# final_sensor_sch_v3.net
KiCad netlist of a schematic drawn in Altium Designer
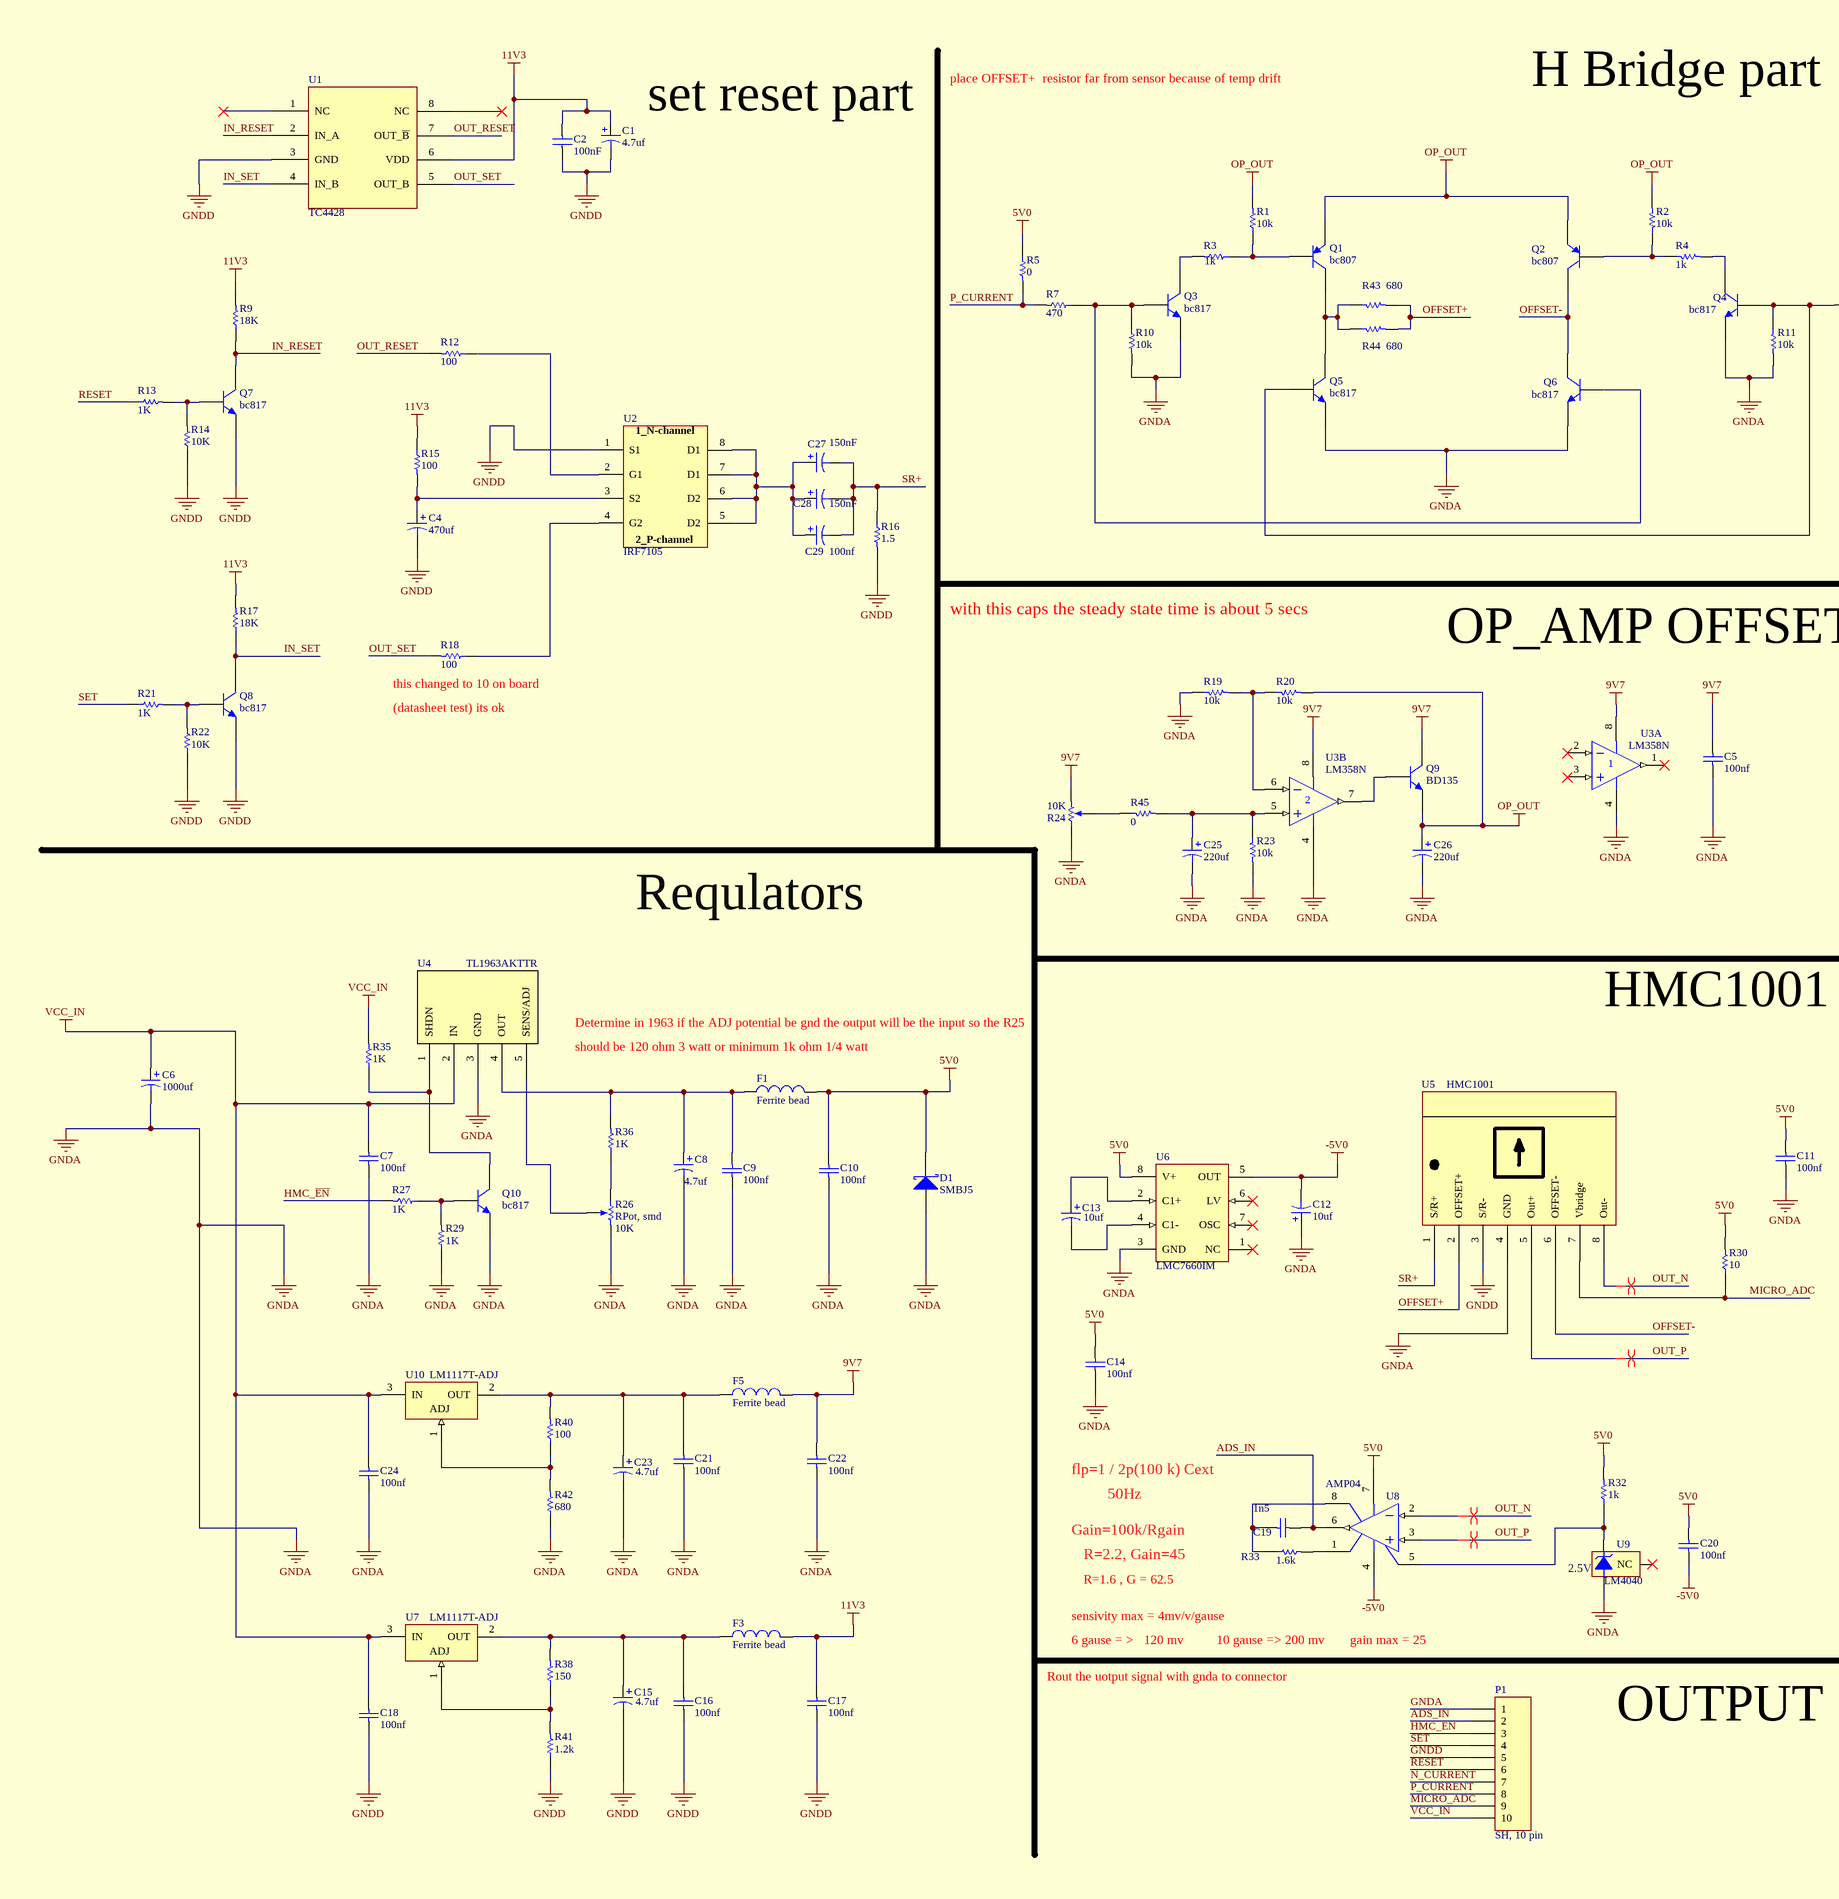
[diagram p0: final_sensor_sch_v3.SchDoc, left]
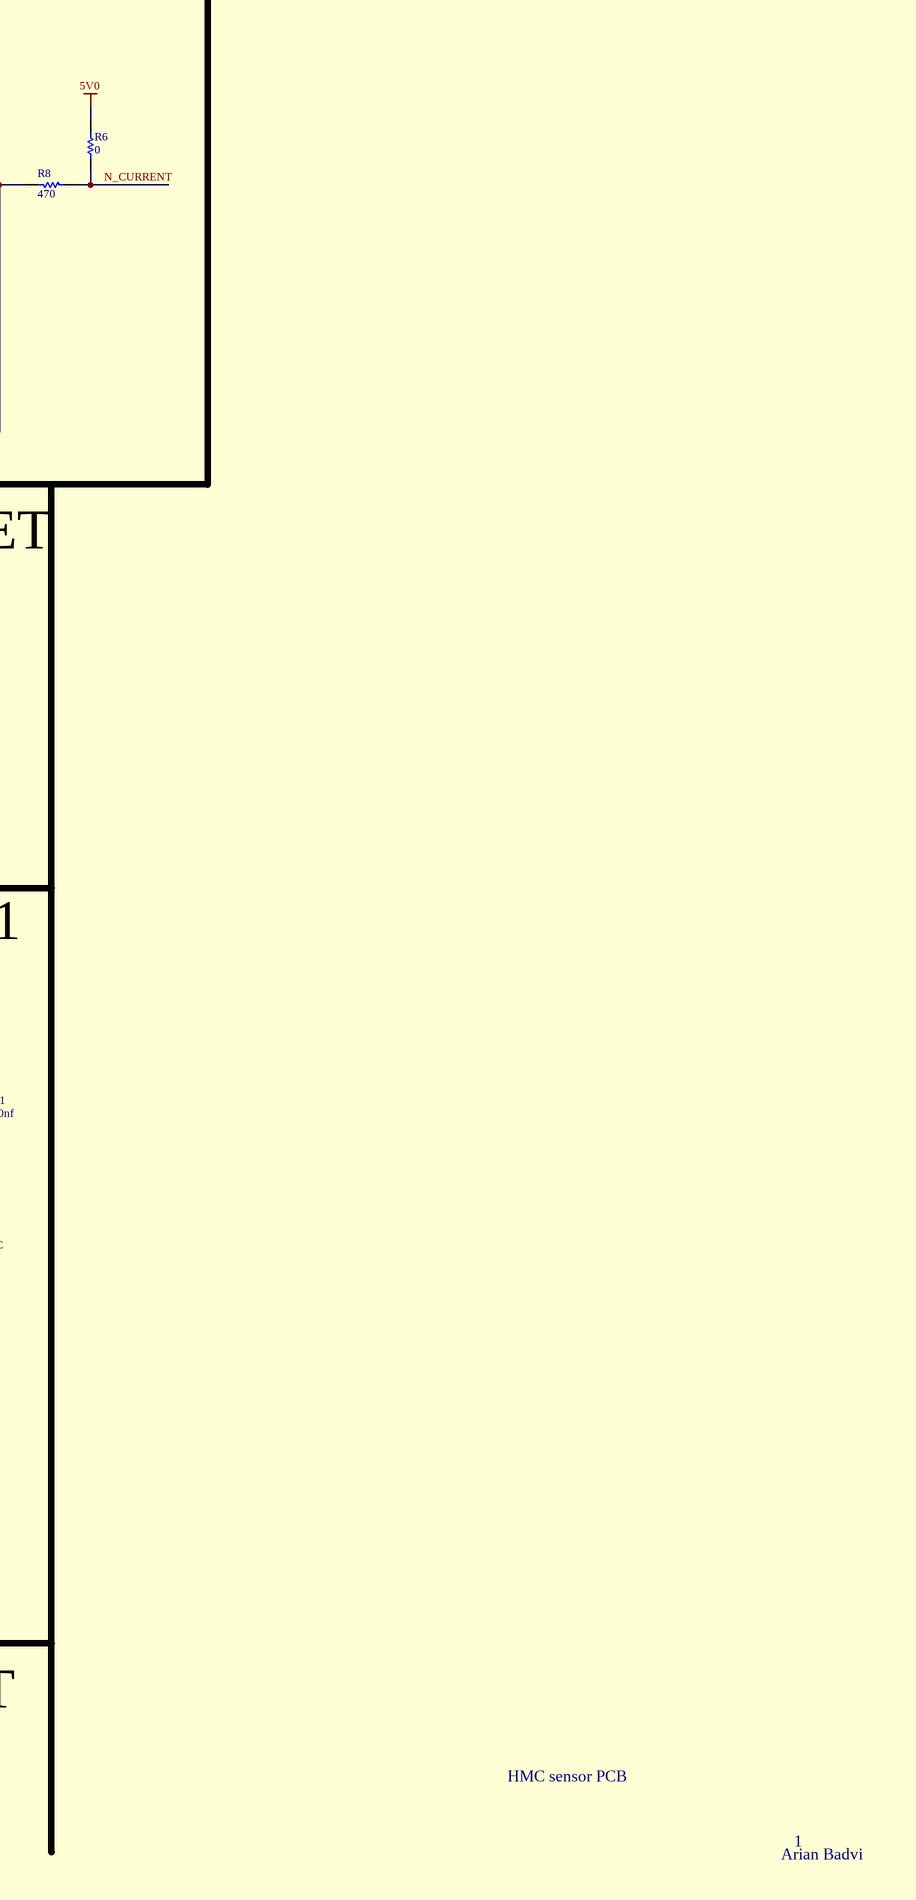
[diagram p1: final_sensor_sch_v3.SchDoc, right]

(export (version "E")
  (design (tool "Eeschema 10.0.6"))
  (components
    (comp (ref "C1")
      (value "4.7uf")
      (footprint "cap_smd_a")
      (description "Polarized Capacitor (Radial)")
      (fields (field (name "PUBLISHER") "Altium Limited"))
      (libsource (lib "") (part "Cap Pol1_1"))
    )
    (comp (ref "C2")
      (value "100nF")
      (footprint "1206")
      (description "Capacitor")
      (fields (field (name "PUBLISHER") "Altium Limited"))
      (libsource (lib "Miscellaneous Devices") (part "Cap"))
    )
    (comp (ref "C4")
      (value "470uf")
      (footprint "cap_smd_d")
      (description "TAN CAP D SIZE")
      (fields (field (name "PUBLISHER") "Altium Limited"))
      (libsource (lib "Miscellaneous Devices") (part "Cap Pol1"))
    )
    (comp (ref "C5")
      (value "100nf")
      (footprint "1206")
      (description "Capacitor")
      (fields (field (name "PUBLISHER") "Altium Limited"))
      (libsource (lib "Miscellaneous Devices") (part "Cap"))
    )
    (comp (ref "C6")
      (value "1000uf")
      (footprint "c_cyl_smd")
      (description "electrolytic smd cap")
      (fields (field (name "PUBLISHER") "Altium Limited"))
      (libsource (lib "Miscellaneous Devices") (part "Cap Pol1"))
    )
    (comp (ref "C7")
      (value "100nf")
      (footprint "1206")
      (description "Capacitor")
      (fields (field (name "PUBLISHER") "Altium Limited"))
      (libsource (lib "Miscellaneous Devices") (part "Cap"))
    )
    (comp (ref "C8")
      (value "4.7uf")
      (footprint "cap_smd_a")
      (description "Polarized Capacitor (Radial)")
      (fields (field (name "PUBLISHER") "Altium Limited"))
      (libsource (lib "Miscellaneous Devices") (part "Cap Pol1"))
    )
    (comp (ref "C9")
      (value "100nf")
      (footprint "1206")
      (description "Capacitor")
      (fields (field (name "PUBLISHER") "Altium Limited"))
      (libsource (lib "Miscellaneous Devices") (part "Cap"))
    )
    (comp (ref "C10")
      (value "100nf")
      (footprint "1206")
      (description "Capacitor")
      (fields (field (name "PUBLISHER") "Altium Limited"))
      (libsource (lib "Miscellaneous Devices") (part "Cap"))
    )
    (comp (ref "C11")
      (value "100nf")
      (footprint "1206")
      (description "Capacitor")
      (fields (field (name "PUBLISHER") "Altium Limited"))
      (libsource (lib "Miscellaneous Devices") (part "Cap"))
    )
    (comp (ref "C12")
      (value "10uf")
      (footprint "cap_smd_a")
      (description "Polarized Capacitor (Radial)")
      (fields (field (name "PUBLISHER") "Altium Limited"))
      (libsource (lib "Miscellaneous Devices") (part "Cap Pol1"))
    )
    (comp (ref "C13")
      (value "10uf")
      (footprint "cap_smd_a")
      (description "Polarized Capacitor (Radial)")
      (fields (field (name "PUBLISHER") "Altium Limited"))
      (libsource (lib "Miscellaneous Devices") (part "Cap Pol1"))
    )
    (comp (ref "C14")
      (value "100nf")
      (footprint "1206")
      (description "Capacitor")
      (fields (field (name "PUBLISHER") "Altium Limited"))
      (libsource (lib "Miscellaneous Devices") (part "Cap"))
    )
    (comp (ref "C15")
      (value "4.7uf")
      (footprint "cap_smd_a")
      (description "Polarized Capacitor (Radial)")
      (fields (field (name "PUBLISHER") "Altium Limited"))
      (libsource (lib "Miscellaneous Devices") (part "Cap Pol1"))
    )
    (comp (ref "C16")
      (value "100nf")
      (footprint "1206")
      (description "Capacitor")
      (fields (field (name "PUBLISHER") "Altium Limited"))
      (libsource (lib "Miscellaneous Devices") (part "Cap"))
    )
    (comp (ref "C17")
      (value "100nf")
      (footprint "1206")
      (description "Capacitor")
      (fields (field (name "PUBLISHER") "Altium Limited"))
      (libsource (lib "Miscellaneous Devices") (part "Cap"))
    )
    (comp (ref "C18")
      (value "100nf")
      (footprint "1206")
      (description "Capacitor")
      (fields (field (name "PUBLISHER") "Altium Limited"))
      (libsource (lib "Miscellaneous Devices") (part "Cap"))
    )
    (comp (ref "C19")
      (value "1n5")
      (footprint "1206")
      (description "Capacitor")
      (fields (field (name "PUBLISHER") "Altium Limited"))
      (libsource (lib "Library") (part "Cap"))
    )
    (comp (ref "C20")
      (value "100nf")
      (footprint "1206")
      (description "Capacitor")
      (fields (field (name "PUBLISHER") "Altium Limited"))
      (libsource (lib "Miscellaneous Devices") (part "Cap"))
    )
    (comp (ref "C21")
      (value "100nf")
      (footprint "1206")
      (description "Capacitor")
      (fields (field (name "PUBLISHER") "Altium Limited"))
      (libsource (lib "Miscellaneous Devices") (part "Cap"))
    )
    (comp (ref "C22")
      (value "100nf")
      (footprint "1206")
      (description "Capacitor")
      (fields (field (name "PUBLISHER") "Altium Limited"))
      (libsource (lib "Miscellaneous Devices") (part "Cap"))
    )
    (comp (ref "C23")
      (value "4.7uf")
      (footprint "cap_smd_a")
      (description "Polarized Capacitor (Radial)")
      (fields (field (name "PUBLISHER") "Altium Limited"))
      (libsource (lib "Miscellaneous Devices") (part "Cap Pol1"))
    )
    (comp (ref "C24")
      (value "100nf")
      (footprint "1206")
      (description "Capacitor")
      (fields (field (name "PUBLISHER") "Altium Limited"))
      (libsource (lib "Miscellaneous Devices") (part "Cap"))
    )
    (comp (ref "C25")
      (value "220uf")
      (footprint "C_CYL_SMD2")
      (description "electrolytic smd cap 16V")
      (fields (field (name "PUBLISHER") "Altium Limited"))
      (libsource (lib "Miscellaneous Devices") (part "Cap Pol1"))
    )
    (comp (ref "C26")
      (value "220uf")
      (footprint "C_CYL_SMD2")
      (description "electrolytic smd cap 16V")
      (fields (field (name "PUBLISHER") "Altium Limited"))
      (libsource (lib "Miscellaneous Devices") (part "Cap Pol1"))
    )
    (comp (ref "C27")
      (value "150nF")
      (footprint "cap_smd_a")
      (description "Polarized Capacitor (Radial)")
      (fields (field (name "PUBLISHER") "Altium Limited"))
      (libsource (lib "Miscellaneous Devices") (part "Cap Pol1"))
    )
    (comp (ref "C28")
      (value "150nF")
      (footprint "cap_smd_a")
      (description "Polarized Capacitor (Radial)")
      (fields (field (name "PUBLISHER") "Altium Limited"))
      (libsource (lib "Miscellaneous Devices") (part "Cap Pol1"))
    )
    (comp (ref "C29")
      (value "100nf")
      (footprint "cap_smd_a")
      (description "Polarized Capacitor (Radial)")
      (fields (field (name "PUBLISHER") "Altium Limited"))
      (libsource (lib "Miscellaneous Devices") (part "Cap Pol1"))
    )
    (comp (ref "D1")
      (value "SMBJ5")
      (footprint "tvs")
      (description "tvs")
      (fields (field (name "PUBLISHER") "Altium Limited"))
      (libsource (lib "Miscellaneous Devices") (part "Diode 10TQ040"))
    )
    (comp (ref "F1")
      (value "Ferrite bead")
      (footprint "1206")
      (description "Ferrite bead, 1206")
      (fields (field (name "PUBLISHER") "Altium Limited"))
      (libsource (lib "Miscellaneous Devices") (part "Inductor"))
    )
    (comp (ref "F3")
      (value "Ferrite bead")
      (footprint "1206")
      (description "Ferrite bead, 1206")
      (fields (field (name "PUBLISHER") "Altium Limited"))
      (libsource (lib "Miscellaneous Devices") (part "Inductor"))
    )
    (comp (ref "F5")
      (value "Ferrite bead")
      (footprint "1206")
      (description "Ferrite bead, 1206")
      (fields (field (name "PUBLISHER") "Altium Limited"))
      (libsource (lib "Miscellaneous Devices") (part "Inductor"))
    )
    (comp (ref "P1")
      (value "SH, 10 pin")
      (footprint "PH_RIGHT_10")
      (description "Header, 10-Pin")
      (fields (field (name "PUBLISHER") "Altium Limited"))
      (libsource (lib "Miscellaneous Connectors") (part "Header 10"))
    )
    (comp (ref "Q1")
      (value "bc807")
      (footprint "sot-23")
      (description "PNP General Purpose Amplifier")
      (fields (field (name "PUBLISHER") "Altium Limited"))
      (libsource (lib "Miscellaneous Devices") (part "2N3906"))
    )
    (comp (ref "Q2")
      (value "bc807")
      (footprint "sot-23")
      (description "PNP General Purpose Amplifier")
      (fields (field (name "PUBLISHER") "Altium Limited"))
      (libsource (lib "Miscellaneous Devices") (part "2N3906"))
    )
    (comp (ref "Q3")
      (value "bc817")
      (footprint "sot-23")
      (description "NPN General Purpose Amplifier")
      (fields (field (name "PUBLISHER") "Altium Limited"))
      (libsource (lib "Miscellaneous Devices") (part "2N3904"))
    )
    (comp (ref "Q4")
      (value "bc817")
      (footprint "sot-23")
      (description "NPN General Purpose Amplifier")
      (fields (field (name "PUBLISHER") "Altium Limited"))
      (libsource (lib "Miscellaneous Devices") (part "2N3904"))
    )
    (comp (ref "Q5")
      (value "bc817")
      (footprint "sot-23")
      (description "NPN General Purpose Amplifier")
      (fields (field (name "PUBLISHER") "Altium Limited"))
      (libsource (lib "Miscellaneous Devices") (part "2N3904"))
    )
    (comp (ref "Q6")
      (value "bc817")
      (footprint "sot-23")
      (description "NPN General Purpose Amplifier")
      (fields (field (name "PUBLISHER") "Altium Limited"))
      (libsource (lib "Miscellaneous Devices") (part "2N3904"))
    )
    (comp (ref "Q7")
      (value "bc817")
      (footprint "sot-23")
      (description "NPN General Purpose Amplifier")
      (fields (field (name "PUBLISHER") "Altium Limited"))
      (libsource (lib "Miscellaneous Devices") (part "2N3904"))
    )
    (comp (ref "Q8")
      (value "bc817")
      (footprint "sot-23")
      (description "NPN General Purpose Amplifier")
      (fields (field (name "PUBLISHER") "Altium Limited"))
      (libsource (lib "Miscellaneous Devices") (part "2N3904"))
    )
    (comp (ref "Q9")
      (value "BD135")
      (footprint "sot-32")
      (description "NPN General Purpose Amplifier")
      (fields (field (name "PUBLISHER") "Altium Limited"))
      (libsource (lib "") (part "2N3904_1"))
    )
    (comp (ref "Q10")
      (value "bc817")
      (footprint "sot-23")
      (description "NPN General Purpose Amplifier")
      (fields (field (name "PUBLISHER") "Altium Limited"))
      (libsource (lib "Miscellaneous Devices") (part "2N3904"))
    )
    (comp (ref "R1")
      (value "10k")
      (footprint "1206")
      (description "Resistor")
      (fields (field (name "PUBLISHER") "Altium Limited"))
      (libsource (lib "Miscellaneous Devices") (part "Res1"))
    )
    (comp (ref "R2")
      (value "10k")
      (footprint "1206")
      (description "Resistor")
      (fields (field (name "PUBLISHER") "Altium Limited"))
      (libsource (lib "Miscellaneous Devices") (part "Res1"))
    )
    (comp (ref "R3")
      (value "1k")
      (footprint "1206")
      (description "Resistor")
      (fields (field (name "PUBLISHER") "Altium Limited"))
      (libsource (lib "Miscellaneous Devices") (part "Res1"))
    )
    (comp (ref "R4")
      (value "1k")
      (footprint "1206")
      (description "Resistor")
      (fields (field (name "PUBLISHER") "Altium Limited"))
      (libsource (lib "Miscellaneous Devices") (part "Res1"))
    )
    (comp (ref "R5")
      (value "0")
      (footprint "1206")
      (description "Resistor")
      (fields (field (name "PUBLISHER") "Altium Limited"))
      (libsource (lib "Miscellaneous Devices") (part "Res1"))
    )
    (comp (ref "R6")
      (value "0")
      (footprint "1206")
      (description "Resistor")
      (fields (field (name "PUBLISHER") "Altium Limited"))
      (libsource (lib "Miscellaneous Devices") (part "Res1"))
    )
    (comp (ref "R7")
      (value "470")
      (footprint "1206")
      (description "Resistor")
      (fields (field (name "PUBLISHER") "Altium Limited"))
      (libsource (lib "Miscellaneous Devices") (part "Res1"))
    )
    (comp (ref "R8")
      (value "470")
      (footprint "1206")
      (description "Resistor")
      (fields (field (name "PUBLISHER") "Altium Limited"))
      (libsource (lib "Miscellaneous Devices") (part "Res1"))
    )
    (comp (ref "R9")
      (value "18K")
      (footprint "1206")
      (description "Resistor")
      (fields (field (name "PUBLISHER") "Altium Limited"))
      (libsource (lib "Miscellaneous Devices") (part "Res1"))
    )
    (comp (ref "R10")
      (value "10k")
      (footprint "1206")
      (description "Resistor")
      (fields (field (name "PUBLISHER") "Altium Limited"))
      (libsource (lib "Miscellaneous Devices") (part "Res1"))
    )
    (comp (ref "R11")
      (value "10k")
      (footprint "1206")
      (description "Resistor")
      (fields (field (name "PUBLISHER") "Altium Limited"))
      (libsource (lib "Miscellaneous Devices") (part "Res1"))
    )
    (comp (ref "R12")
      (value "100")
      (footprint "1206")
      (description "Resistor")
      (fields (field (name "PUBLISHER") "Altium Limited"))
      (libsource (lib "Miscellaneous Devices") (part "Res1"))
    )
    (comp (ref "R13")
      (value "1K")
      (footprint "1206")
      (description "Resistor")
      (fields (field (name "PUBLISHER") "Altium Limited"))
      (libsource (lib "Miscellaneous Devices") (part "Res1"))
    )
    (comp (ref "R14")
      (value "10K")
      (footprint "1206")
      (description "Resistor")
      (fields (field (name "PUBLISHER") "Altium Limited"))
      (libsource (lib "Miscellaneous Devices") (part "Res1"))
    )
    (comp (ref "R15")
      (value "100")
      (footprint "1206")
      (description "Resistor")
      (fields (field (name "PUBLISHER") "Altium Limited"))
      (libsource (lib "Miscellaneous Devices") (part "Res1"))
    )
    (comp (ref "R16")
      (value "1.5")
      (footprint "1206")
      (description "Resistor")
      (fields (field (name "PUBLISHER") "Altium Limited"))
      (libsource (lib "Miscellaneous Devices") (part "Res1"))
    )
    (comp (ref "R17")
      (value "18K")
      (footprint "1206")
      (description "Resistor")
      (fields (field (name "PUBLISHER") "Altium Limited"))
      (libsource (lib "Miscellaneous Devices") (part "Res1"))
    )
    (comp (ref "R18")
      (value "100")
      (footprint "1206")
      (description "Resistor")
      (fields (field (name "PUBLISHER") "Altium Limited"))
      (libsource (lib "Miscellaneous Devices") (part "Res1"))
    )
    (comp (ref "R19")
      (value "10k")
      (footprint "1206")
      (description "Resistor")
      (fields (field (name "PUBLISHER") "Altium Limited"))
      (libsource (lib "") (part "Res1_1"))
    )
    (comp (ref "R20")
      (value "10k")
      (footprint "1206")
      (description "Resistor")
      (fields (field (name "PUBLISHER") "Altium Limited"))
      (libsource (lib "") (part "Res1_1"))
    )
    (comp (ref "R21")
      (value "1K")
      (footprint "1206")
      (description "Resistor")
      (fields (field (name "PUBLISHER") "Altium Limited"))
      (libsource (lib "Miscellaneous Devices") (part "Res1"))
    )
    (comp (ref "R22")
      (value "10K")
      (footprint "1206")
      (description "Resistor")
      (fields (field (name "PUBLISHER") "Altium Limited"))
      (libsource (lib "Miscellaneous Devices") (part "Res1"))
    )
    (comp (ref "R23")
      (value "10k")
      (footprint "1206")
      (description "Resistor")
      (fields (field (name "PUBLISHER") "Altium Limited"))
      (libsource (lib "Miscellaneous Devices") (part "Res1"))
    )
    (comp (ref "R24")
      (value "10K")
      (footprint "pot")
      (description "Potentiometer")
      (fields (field (name "Comment") "RPot") (field (name "PUBLISHER") "Altium Limited"))
      (libsource (lib "Miscellaneous Devices") (part "RPot"))
    )
    (comp (ref "R26")
      (value "RPot, smd")
      (footprint "pot smd")
      (description "Potentiometer")
      (fields (field (name "ALTIUM_VALUE") "10K") (field (name "PUBLISHER") "Altium Limited"))
      (libsource (lib "Miscellaneous Devices") (part "RPot"))
    )
    (comp (ref "R27")
      (value "1K")
      (footprint "1206")
      (description "Resistor")
      (fields (field (name "PUBLISHER") "Altium Limited"))
      (libsource (lib "Miscellaneous Devices") (part "Res1"))
    )
    (comp (ref "R29")
      (value "1K")
      (footprint "1206")
      (description "Resistor")
      (fields (field (name "PUBLISHER") "Altium Limited"))
      (libsource (lib "Miscellaneous Devices") (part "Res1"))
    )
    (comp (ref "R30")
      (value "10")
      (footprint "1206")
      (description "Resistor, 1/4W")
      (fields (field (name "PUBLISHER") "Seyed Razi Vesali") (field (name "EMAIL") "razi.vesali@gmail.com"))
      (libsource (lib "resistor1") (part "Resistor"))
    )
    (comp (ref "R32")
      (value "1k")
      (footprint "1206")
      (description "Resistor, 1/4W")
      (fields (field (name "PUBLISHER") "Seyed Razi Vesali") (field (name "EMAIL") "razi.vesali@gmail.com"))
      (libsource (lib "resistor1") (part "Resistor"))
    )
    (comp (ref "R33")
      (value "1.6k")
      (footprint "1206")
      (description "General Resistor")
      (fields (field (name "PUBLISHER") "Altium Limited"))
      (libsource (lib "Library") (part "Resistor"))
    )
    (comp (ref "R35")
      (value "1K")
      (footprint "1206")
      (description "Resistor")
      (fields (field (name "PUBLISHER") "Altium Limited"))
      (libsource (lib "Miscellaneous Devices") (part "Res1"))
    )
    (comp (ref "R36")
      (value "1K")
      (footprint "1206")
      (description "Resistor, 1/4W")
      (fields (field (name "PUBLISHER") "Seyed Razi Vesali") (field (name "EMAIL") "razi.vesali@gmail.com"))
      (libsource (lib "resistor1") (part "Resistor"))
    )
    (comp (ref "R38")
      (value "150")
      (footprint "1206")
      (description "Resistor, 1/4W")
      (fields (field (name "PUBLISHER") "Seyed Razi Vesali") (field (name "EMAIL") "razi.vesali@gmail.com"))
      (libsource (lib "resistor1") (part "Resistor"))
    )
    (comp (ref "R40")
      (value "100")
      (footprint "1206")
      (description "Resistor, 1/4W")
      (fields (field (name "PUBLISHER") "Seyed Razi Vesali") (field (name "EMAIL") "razi.vesali@gmail.com"))
      (libsource (lib "resistor1") (part "Resistor"))
    )
    (comp (ref "R41")
      (value "1.2k")
      (footprint "1206")
      (description "Resistor, 1/4W")
      (fields (field (name "PUBLISHER") "Seyed Razi Vesali") (field (name "EMAIL") "razi.vesali@gmail.com"))
      (libsource (lib "resistor1") (part "Resistor"))
    )
    (comp (ref "R42")
      (value "680")
      (footprint "1206")
      (description "Resistor, 1/4W")
      (fields (field (name "PUBLISHER") "Seyed Razi Vesali") (field (name "EMAIL") "razi.vesali@gmail.com"))
      (libsource (lib "resistor1") (part "Resistor"))
    )
    (comp (ref "R43")
      (value "680")
      (footprint "1206")
      (description "Resistor")
      (fields (field (name "PUBLISHER") "Altium Limited"))
      (libsource (lib "Miscellaneous Devices") (part "Res1"))
    )
    (comp (ref "R44")
      (value "680")
      (footprint "1206")
      (description "Resistor")
      (fields (field (name "PUBLISHER") "Altium Limited"))
      (libsource (lib "Miscellaneous Devices") (part "Res1"))
    )
    (comp (ref "R45")
      (value "0")
      (footprint "1206")
      (description "Resistor")
      (fields (field (name "PUBLISHER") "Altium Limited"))
      (libsource (lib "") (part "Res1_1"))
    )
    (comp (ref "U1") (value "TC4428") (footprint "sop8") (libsource (lib "tc4428") (part "TC4428")))
    (comp (ref "U2") (value "IRF7105") (footprint "sop8") (libsource (lib "irf7106") (part "IRF7106")))
    (comp (ref "U3")
      (value "LM358N")
      (footprint "sop8")
      (description "Dual Low-Power Operational Amplifier")
      (fields (field (name "PUBLISHER") "Altium Limited"))
      (libsource (lib "Motorola Amplifier Operational Amplifier") (part "LM358N"))
    )
    (comp (ref "U4") (value "TL1963AKTTR") (footprint "tl1963") (libsource (lib "Library") (part "TL1963")))
    (comp (ref "U5") (value "HMC1001") (footprint "HMC1001") (libsource (lib "Library") (part "HMC1001")))
    (comp (ref "U6")
      (value "LMC7660IM")
      (footprint "sop8")
      (description "Switched Capacitor Voltage Converter")
      (fields
        (field (name "MANUFACTURER") "National Semiconductor")
        (field (name "DIGIKEYPARTNUMBER") "LMC7660IM-ND")
        (field (name "PUBLISHER") "Altium Limited")
      )
      (libsource (lib "NSC Switch Caps") (part "LMC7660IM"))
    )
    (comp (ref "U7")
      (value "LM1117T-ADJ")
      (footprint "dpak")
      (description "800mA Low-Dropout Linear Regulator")
      (fields
        (field (name "MANUFACTURER") "National Semiconductor")
        (field (name "DIGIKEYPARTNUMBER") "LM1117T-ADJ-ND")
        (field (name "PUBLISHER") "Altium Limited")
      )
      (libsource (lib "NSC LDO") (part "LM1117T-ADJ"))
    )
    (comp (ref "U8")
      (value "AMP04")
      (footprint "sop8")
      (fields (field (name "PUBLISHER") "Altium Limited"))
      (libsource (lib "Miscellaneous Devices") (part "Op Amp"))
    )
    (comp (ref "U9")
      (value "LM4040")
      (footprint "sot-23")
      (description "Precision Micropower Shunt Voltage Reference, 3-pin SOT-23")
      (fields
        (field (name "PARTNUMBER") "LM4040DIM3-10.0")
        (field (name "MANUFACTURER") "National Semiconductor")
        (field (name "PUBLISHER") "Altium Limited")
      )
      (libsource (lib "final_sensor_sch_lib") (part "LM4040"))
    )
    (comp (ref "U10")
      (value "LM1117T-ADJ")
      (footprint "dpak")
      (description "800mA Low-Dropout Linear Regulator")
      (fields
        (field (name "MANUFACTURER") "National Semiconductor")
        (field (name "DIGIKEYPARTNUMBER") "LM1117T-ADJ-ND")
        (field (name "PUBLISHER") "Altium Limited")
      )
      (libsource (lib "NSC LDO") (part "LM1117T-ADJ"))
    )
  )
  (nets
    (net (code "1") (name "-5V0") (class "Default")
      (node (ref "C12") (pin "2") (pinfunction "2_2") (pintype "passive"))
      (node (ref "C20") (pin "1") (pinfunction "1_1") (pintype "passive"))
      (node (ref "U6") (pin "5") (pinfunction "OUT_5") (pintype "power_in"))
      (node (ref "U8") (pin "4") (pinfunction "V-_4") (pintype "power_in"))
    )
    (net (code "2") (name "/ADS_IN") (class "Default")
      (node (ref "C19") (pin "1") (pinfunction "1_1") (pintype "passive"))
      (node (ref "P1") (pin "2") (pinfunction "2_2") (pintype "passive"))
      (node (ref "U8") (pin "6") (pinfunction "OUT_6") (pintype "output"))
    )
    (net (code "3") (name "/HMC_~{EN}") (class "Default")
      (node (ref "P1") (pin "3") (pinfunction "3_3") (pintype "passive"))
      (node (ref "R27") (pin "2") (pinfunction "2_2") (pintype "passive"))
    )
    (net (code "4") (name "/IN_RESET") (class "Default")
      (node (ref "Q7") (pin "3") (pinfunction "C_3") (pintype "passive"))
      (node (ref "R9") (pin "1") (pinfunction "1_1") (pintype "passive"))
      (node (ref "U1") (pin "2") (pinfunction "IN_A_2") (pintype "passive"))
    )
    (net (code "5") (name "/IN_SET") (class "Default")
      (node (ref "Q8") (pin "3") (pinfunction "C_3") (pintype "passive"))
      (node (ref "R17") (pin "1") (pinfunction "1_1") (pintype "passive"))
      (node (ref "U1") (pin "4") (pinfunction "IN_B_4") (pintype "passive"))
    )
    (net (code "6") (name "/MICRO_ADC") (class "Default")
      (node (ref "P1") (pin "9") (pinfunction "9_9") (pintype "passive"))
      (node (ref "R30") (pin "1") (pinfunction "1_1") (pintype "passive"))
      (node (ref "U5") (pin "7") (pinfunction "Vbridge_7") (pintype "passive"))
    )
    (net (code "7") (name "/N_CURRENT") (class "Default")
      (node (ref "P1") (pin "7") (pinfunction "7_7") (pintype "passive"))
      (node (ref "R6") (pin "2") (pinfunction "2_2") (pintype "passive"))
      (node (ref "R8") (pin "2") (pinfunction "2_2") (pintype "passive"))
    )
    (net (code "8") (name "/OFFSET+") (class "Default")
      (node (ref "R43") (pin "2") (pinfunction "2_2") (pintype "passive"))
      (node (ref "R44") (pin "2") (pinfunction "2_2") (pintype "passive"))
      (node (ref "U5") (pin "2") (pinfunction "OFFSET+_2") (pintype "passive"))
    )
    (net (code "9") (name "/OFFSET-") (class "Default")
      (node (ref "Q2") (pin "3") (pinfunction "C_3") (pintype "passive"))
      (node (ref "Q6") (pin "3") (pinfunction "C_3") (pintype "passive"))
      (node (ref "U5") (pin "6") (pinfunction "OFFSET-_6") (pintype "passive"))
    )
    (net (code "10") (name "/OUT_N") (class "Default")
      (node (ref "U5") (pin "8") (pinfunction "Out-_8") (pintype "passive"))
      (node (ref "U8") (pin "2") (pinfunction "IN-_2") (pintype "input"))
    )
    (net (code "11") (name "/OUT_P") (class "Default")
      (node (ref "U5") (pin "5") (pinfunction "Out+_5") (pintype "passive"))
      (node (ref "U8") (pin "3") (pinfunction "IN+_3") (pintype "input"))
    )
    (net (code "12") (name "/OUT_RESET") (class "Default")
      (node (ref "R12") (pin "2") (pinfunction "2_2") (pintype "passive"))
      (node (ref "U1") (pin "7") (pinfunction "OUT_~{B}_7") (pintype "passive"))
    )
    (net (code "13") (name "/OUT_SET") (class "Default")
      (node (ref "R18") (pin "2") (pinfunction "2_2") (pintype "passive"))
      (node (ref "U1") (pin "5") (pinfunction "OUT_B_5") (pintype "passive"))
    )
    (net (code "14") (name "/P_CURRENT") (class "Default")
      (node (ref "P1") (pin "8") (pinfunction "8_8") (pintype "passive"))
      (node (ref "R5") (pin "2") (pinfunction "2_2") (pintype "passive"))
      (node (ref "R7") (pin "2") (pinfunction "2_2") (pintype "passive"))
    )
    (net (code "15") (name "/RESET") (class "Default")
      (node (ref "P1") (pin "6") (pinfunction "6_6") (pintype "passive"))
      (node (ref "R13") (pin "1") (pinfunction "1_1") (pintype "passive"))
    )
    (net (code "16") (name "/SET") (class "Default")
      (node (ref "P1") (pin "4") (pinfunction "4_4") (pintype "passive"))
      (node (ref "R21") (pin "1") (pinfunction "1_1") (pintype "passive"))
    )
    (net (code "17") (name "/SR+") (class "Default")
      (node (ref "C27") (pin "2") (pinfunction "2_2") (pintype "passive"))
      (node (ref "C28") (pin "2") (pinfunction "2_2") (pintype "passive"))
      (node (ref "C29") (pin "2") (pinfunction "2_2") (pintype "passive"))
      (node (ref "R16") (pin "1") (pinfunction "1_1") (pintype "passive"))
      (node (ref "U5") (pin "1") (pinfunction "S/R+_1") (pintype "passive"))
    )
    (net (code "18") (name "5V0") (class "Default")
      (node (ref "C10") (pin "2") (pinfunction "2_2") (pintype "passive"))
      (node (ref "C11") (pin "2") (pinfunction "2_2") (pintype "passive"))
      (node (ref "C14") (pin "2") (pinfunction "2_2") (pintype "passive"))
      (node (ref "C20") (pin "2") (pinfunction "2_2") (pintype "passive"))
      (node (ref "D1") (pin "2") (pinfunction "K_2") (pintype "passive"))
      (node (ref "F1") (pin "2") (pinfunction "2_2") (pintype "passive"))
      (node (ref "R30") (pin "2") (pinfunction "2_2") (pintype "passive"))
      (node (ref "R32") (pin "2") (pinfunction "2_2") (pintype "passive"))
      (node (ref "R5") (pin "1") (pinfunction "1_1") (pintype "passive"))
      (node (ref "R6") (pin "1") (pinfunction "1_1") (pintype "passive"))
      (node (ref "U6") (pin "8") (pinfunction "V+_8") (pintype "power_in"))
      (node (ref "U8") (pin "7") (pinfunction "V+_7") (pintype "power_in"))
    )
    (net (code "19") (name "9V7") (class "Default")
      (node (ref "C22") (pin "2") (pinfunction "2_2") (pintype "passive"))
      (node (ref "C5") (pin "2") (pinfunction "2_2") (pintype "passive"))
      (node (ref "F5") (pin "2") (pinfunction "2_2") (pintype "passive"))
      (node (ref "Q9") (pin "2") (pinfunction "C_2") (pintype "passive"))
      (node (ref "R24") (pin "3") (pinfunction "BOT_3") (pintype "passive"))
      (node (ref "U3") (pin "8") (pinfunction "V+_8") (pintype "power_in"))
    )
    (net (code "20") (name "11V3") (class "Default")
      (node (ref "C1") (pin "1") (pinfunction "1_1") (pintype "passive"))
      (node (ref "C17") (pin "2") (pinfunction "2_2") (pintype "passive"))
      (node (ref "C2") (pin "1") (pinfunction "1_1") (pintype "passive"))
      (node (ref "F3") (pin "2") (pinfunction "2_2") (pintype "passive"))
      (node (ref "R15") (pin "1") (pinfunction "1_1") (pintype "passive"))
      (node (ref "R17") (pin "2") (pinfunction "2_2") (pintype "passive"))
      (node (ref "R9") (pin "2") (pinfunction "2_2") (pintype "passive"))
      (node (ref "U1") (pin "6") (pinfunction "VDD_6") (pintype "passive"))
    )
    (net (code "21") (name "GNDA") (class "Default")
      (node (ref "C10") (pin "1") (pinfunction "1_1") (pintype "passive"))
      (node (ref "C11") (pin "1") (pinfunction "1_1") (pintype "passive"))
      (node (ref "C12") (pin "1") (pinfunction "1_1") (pintype "passive"))
      (node (ref "C14") (pin "1") (pinfunction "1_1") (pintype "passive"))
      (node (ref "C21") (pin "1") (pinfunction "1_1") (pintype "passive"))
      (node (ref "C22") (pin "1") (pinfunction "1_1") (pintype "passive"))
      (node (ref "C23") (pin "2") (pinfunction "2_2") (pintype "passive"))
      (node (ref "C24") (pin "1") (pinfunction "1_1") (pintype "passive"))
      (node (ref "C25") (pin "2") (pinfunction "2_2") (pintype "passive"))
      (node (ref "C26") (pin "2") (pinfunction "2_2") (pintype "passive"))
      (node (ref "C5") (pin "1") (pinfunction "1_1") (pintype "passive"))
      (node (ref "C6") (pin "2") (pinfunction "2_2") (pintype "passive"))
      (node (ref "C7") (pin "1") (pinfunction "1_1") (pintype "passive"))
      (node (ref "C8") (pin "2") (pinfunction "2_2") (pintype "passive"))
      (node (ref "C9") (pin "1") (pinfunction "1_1") (pintype "passive"))
      (node (ref "D1") (pin "1") (pinfunction "A_1") (pintype "passive"))
      (node (ref "P1") (pin "1") (pinfunction "1_1") (pintype "passive"))
      (node (ref "Q10") (pin "2") (pinfunction "E_2") (pintype "passive"))
      (node (ref "Q3") (pin "2") (pinfunction "E_2") (pintype "passive"))
      (node (ref "Q4") (pin "2") (pinfunction "E_2") (pintype "passive"))
      (node (ref "Q5") (pin "2") (pinfunction "E_2") (pintype "passive"))
      (node (ref "Q6") (pin "2") (pinfunction "E_2") (pintype "passive"))
      (node (ref "R10") (pin "2") (pinfunction "2_2") (pintype "passive"))
      (node (ref "R11") (pin "2") (pinfunction "2_2") (pintype "passive"))
      (node (ref "R19") (pin "1") (pinfunction "1_1") (pintype "passive"))
      (node (ref "R23") (pin "2") (pinfunction "2_2") (pintype "passive"))
      (node (ref "R24") (pin "1") (pinfunction "TOP_1") (pintype "passive"))
      (node (ref "R26") (pin "3") (pinfunction "BOT_3") (pintype "passive"))
      (node (ref "R29") (pin "1") (pinfunction "1_1") (pintype "passive"))
      (node (ref "R42") (pin "1") (pinfunction "1_1") (pintype "passive"))
      (node (ref "U3") (pin "4") (pinfunction "V-_4") (pintype "power_in"))
      (node (ref "U4") (pin "3") (pinfunction "GND_3") (pintype "passive"))
      (node (ref "U5") (pin "4") (pinfunction "GND_4") (pintype "passive"))
      (node (ref "U6") (pin "3") (pinfunction "GND_3") (pintype "power_in"))
      (node (ref "U9") (pin "2") (pinfunction "-V_2") (pintype "passive"))
    )
    (net (code "22") (name "GNDD") (class "Default")
      (node (ref "C1") (pin "2") (pinfunction "2_2") (pintype "passive"))
      (node (ref "C15") (pin "2") (pinfunction "2_2") (pintype "passive"))
      (node (ref "C16") (pin "1") (pinfunction "1_1") (pintype "passive"))
      (node (ref "C17") (pin "1") (pinfunction "1_1") (pintype "passive"))
      (node (ref "C18") (pin "1") (pinfunction "1_1") (pintype "passive"))
      (node (ref "C2") (pin "2") (pinfunction "2_2") (pintype "passive"))
      (node (ref "C4") (pin "2") (pinfunction "2_2") (pintype "passive"))
      (node (ref "P1") (pin "5") (pinfunction "5_5") (pintype "passive"))
      (node (ref "Q7") (pin "2") (pinfunction "E_2") (pintype "passive"))
      (node (ref "Q8") (pin "2") (pinfunction "E_2") (pintype "passive"))
      (node (ref "R14") (pin "1") (pinfunction "1_1") (pintype "passive"))
      (node (ref "R16") (pin "2") (pinfunction "2_2") (pintype "passive"))
      (node (ref "R22") (pin "1") (pinfunction "1_1") (pintype "passive"))
      (node (ref "R41") (pin "1") (pinfunction "1_1") (pintype "passive"))
      (node (ref "U1") (pin "3") (pinfunction "GND_3") (pintype "passive"))
      (node (ref "U2") (pin "1") (pinfunction "S1_1") (pintype "passive"))
      (node (ref "U5") (pin "3") (pinfunction "S/R-_3") (pintype "passive"))
    )
    (net (code "23") (name "Net-(C27-Pad1)") (class "Default")
      (node (ref "C27") (pin "1") (pinfunction "1_1") (pintype "passive"))
      (node (ref "C28") (pin "1") (pinfunction "1_1") (pintype "passive"))
      (node (ref "C29") (pin "1") (pinfunction "1_1") (pintype "passive"))
      (node (ref "U2") (pin "5") (pinfunction "D2_5") (pintype "passive"))
      (node (ref "U2") (pin "6") (pinfunction "D2_6") (pintype "passive"))
      (node (ref "U2") (pin "7") (pinfunction "D1_7") (pintype "passive"))
      (node (ref "U2") (pin "8") (pinfunction "D1_8") (pintype "passive"))
    )
    (net (code "24") (name "Net-(Q1-B)") (class "Default")
      (node (ref "Q1") (pin "1") (pinfunction "B_1") (pintype "passive"))
      (node (ref "R1") (pin "1") (pinfunction "1_1") (pintype "passive"))
      (node (ref "R3") (pin "1") (pinfunction "1_1") (pintype "passive"))
    )
    (net (code "25") (name "Net-(Q1-C)") (class "Default")
      (node (ref "Q1") (pin "3") (pinfunction "C_3") (pintype "passive"))
      (node (ref "Q5") (pin "3") (pinfunction "C_3") (pintype "passive"))
      (node (ref "R43") (pin "1") (pinfunction "1_1") (pintype "passive"))
      (node (ref "R44") (pin "1") (pinfunction "1_1") (pintype "passive"))
    )
    (net (code "26") (name "Net-(Q2-B)") (class "Default")
      (node (ref "Q2") (pin "1") (pinfunction "B_1") (pintype "passive"))
      (node (ref "R2") (pin "1") (pinfunction "1_1") (pintype "passive"))
      (node (ref "R4") (pin "1") (pinfunction "1_1") (pintype "passive"))
    )
    (net (code "27") (name "Net-(Q3-B)") (class "Default")
      (node (ref "Q3") (pin "1") (pinfunction "B_1") (pintype "passive"))
      (node (ref "Q6") (pin "1") (pinfunction "B_1") (pintype "passive"))
      (node (ref "R10") (pin "1") (pinfunction "1_1") (pintype "passive"))
      (node (ref "R7") (pin "1") (pinfunction "1_1") (pintype "passive"))
    )
    (net (code "28") (name "Net-(Q3-C)") (class "Default")
      (node (ref "Q3") (pin "3") (pinfunction "C_3") (pintype "passive"))
      (node (ref "R3") (pin "2") (pinfunction "2_2") (pintype "passive"))
    )
    (net (code "29") (name "Net-(Q4-B)") (class "Default")
      (node (ref "Q4") (pin "1") (pinfunction "B_1") (pintype "passive"))
      (node (ref "Q5") (pin "1") (pinfunction "B_1") (pintype "passive"))
      (node (ref "R11") (pin "1") (pinfunction "1_1") (pintype "passive"))
      (node (ref "R8") (pin "1") (pinfunction "1_1") (pintype "passive"))
    )
    (net (code "30") (name "Net-(Q4-C)") (class "Default")
      (node (ref "Q4") (pin "3") (pinfunction "C_3") (pintype "passive"))
      (node (ref "R4") (pin "2") (pinfunction "2_2") (pintype "passive"))
    )
    (net (code "31") (name "Net-(Q7-B)") (class "Default")
      (node (ref "Q7") (pin "1") (pinfunction "B_1") (pintype "passive"))
      (node (ref "R13") (pin "2") (pinfunction "2_2") (pintype "passive"))
      (node (ref "R14") (pin "2") (pinfunction "2_2") (pintype "passive"))
    )
    (net (code "32") (name "Net-(Q8-B)") (class "Default")
      (node (ref "Q8") (pin "1") (pinfunction "B_1") (pintype "passive"))
      (node (ref "R21") (pin "2") (pinfunction "2_2") (pintype "passive"))
      (node (ref "R22") (pin "2") (pinfunction "2_2") (pintype "passive"))
    )
    (net (code "33") (name "Net-(Q9-B)") (class "Default")
      (node (ref "Q9") (pin "1") (pinfunction "B_1") (pintype "passive"))
      (node (ref "U3") (pin "7") (pinfunction "OUT_7") (pintype "output"))
    )
    (net (code "34") (name "Net-(Q10-B)") (class "Default")
      (node (ref "Q10") (pin "1") (pinfunction "B_1") (pintype "passive"))
      (node (ref "R27") (pin "1") (pinfunction "1_1") (pintype "passive"))
      (node (ref "R29") (pin "2") (pinfunction "2_2") (pintype "passive"))
    )
    (net (code "35") (name "Net-(Q10-C)") (class "Default")
      (node (ref "Q10") (pin "3") (pinfunction "C_3") (pintype "passive"))
      (node (ref "R35") (pin "1") (pinfunction "1_1") (pintype "passive"))
      (node (ref "U4") (pin "1") (pinfunction "SHDN_1") (pintype "passive"))
    )
    (net (code "36") (name "Net-(R24-TAP)") (class "Default")
      (node (ref "R24") (pin "2") (pinfunction "TAP_2") (pintype "passive"))
      (node (ref "R45") (pin "1") (pinfunction "1_1") (pintype "passive"))
    )
    (net (code "37") (name "Net-(R26-TAP)") (class "Default")
      (node (ref "R26") (pin "2") (pinfunction "TAP_2") (pintype "passive"))
      (node (ref "U4") (pin "5") (pinfunction "SENS/ADJ_5") (pintype "passive"))
    )
    (net (code "38") (name "Net-(R26-TOP)") (class "Default")
      (node (ref "R26") (pin "1") (pinfunction "TOP_1") (pintype "passive"))
      (node (ref "R36") (pin "1") (pinfunction "1_1") (pintype "passive"))
    )
    (net (code "39") (name "Net-(R33-Pad2)") (class "Default")
      (node (ref "R33") (pin "2") (pinfunction "2_2") (pintype "passive"))
      (node (ref "U8") (pin "1") (pinfunction "OS_NUL_1") (pintype "passive"))
    )
    (net (code "40") (name "Net-(U2-G1)") (class "Default")
      (node (ref "R12") (pin "1") (pinfunction "1_1") (pintype "passive"))
      (node (ref "U2") (pin "2") (pinfunction "G1_2") (pintype "passive"))
    )
    (net (code "41") (name "Net-(U2-G2)") (class "Default")
      (node (ref "R18") (pin "1") (pinfunction "1_1") (pintype "passive"))
      (node (ref "U2") (pin "4") (pinfunction "G2_4") (pintype "passive"))
    )
    (net (code "42") (name "Net-(U2-S2)") (class "Default")
      (node (ref "C4") (pin "1") (pinfunction "1_1") (pintype "passive"))
      (node (ref "R15") (pin "2") (pinfunction "2_2") (pintype "passive"))
      (node (ref "U2") (pin "3") (pinfunction "S2_3") (pintype "passive"))
    )
    (net (code "43") (name "Net-(U3B-IN+)") (class "Default")
      (node (ref "C25") (pin "1") (pinfunction "1_1") (pintype "passive"))
      (node (ref "R23") (pin "1") (pinfunction "1_1") (pintype "passive"))
      (node (ref "R45") (pin "2") (pinfunction "2_2") (pintype "passive"))
      (node (ref "U3") (pin "5") (pinfunction "IN+_5") (pintype "input"))
    )
    (net (code "44") (name "Net-(U3B-IN-)") (class "Default")
      (node (ref "R19") (pin "2") (pinfunction "2_2") (pintype "passive"))
      (node (ref "R20") (pin "1") (pinfunction "1_1") (pintype "passive"))
      (node (ref "U3") (pin "6") (pinfunction "IN-_6") (pintype "input"))
    )
    (net (code "45") (name "Net-(U4-OUT)") (class "Default")
      (node (ref "C8") (pin "1") (pinfunction "1_1") (pintype "passive"))
      (node (ref "C9") (pin "2") (pinfunction "2_2") (pintype "passive"))
      (node (ref "F1") (pin "1") (pinfunction "1_1") (pintype "passive"))
      (node (ref "R36") (pin "2") (pinfunction "2_2") (pintype "passive"))
      (node (ref "U4") (pin "4") (pinfunction "OUT_4") (pintype "passive"))
    )
    (net (code "46") (name "Net-(U6-C1+)") (class "Default")
      (node (ref "C13") (pin "1") (pinfunction "1_1") (pintype "passive"))
      (node (ref "U6") (pin "2") (pinfunction "C1+_2") (pintype "input"))
    )
    (net (code "47") (name "Net-(U6-C1-)") (class "Default")
      (node (ref "C13") (pin "2") (pinfunction "2_2") (pintype "passive"))
      (node (ref "U6") (pin "4") (pinfunction "C1-_4") (pintype "input"))
    )
    (net (code "48") (name "Net-(U7-ADJ)") (class "Default")
      (node (ref "R38") (pin "1") (pinfunction "1_1") (pintype "passive"))
      (node (ref "R41") (pin "2") (pinfunction "2_2") (pintype "passive"))
      (node (ref "U7") (pin "1") (pinfunction "ADJ_1") (pintype "input"))
    )
    (net (code "49") (name "Net-(U7-OUT)") (class "Default")
      (node (ref "C15") (pin "1") (pinfunction "1_1") (pintype "passive"))
      (node (ref "C16") (pin "2") (pinfunction "2_2") (pintype "passive"))
      (node (ref "F3") (pin "1") (pinfunction "1_1") (pintype "passive"))
      (node (ref "R38") (pin "2") (pinfunction "2_2") (pintype "passive"))
      (node (ref "U7") (pin "2") (pinfunction "OUT_2") (pintype "power_in"))
    )
    (net (code "50") (name "Net-(U8-TAB)") (class "Default")
      (node (ref "C19") (pin "2") (pinfunction "2_2") (pintype "passive"))
      (node (ref "R33") (pin "1") (pinfunction "1_1") (pintype "passive"))
      (node (ref "U8") (pin "8") (pinfunction "TAB_8") (pintype "passive"))
    )
    (net (code "51") (name "Net-(U9-+V)") (class "Default")
      (node (ref "R32") (pin "1") (pinfunction "1_1") (pintype "passive"))
      (node (ref "U8") (pin "5") (pinfunction "OS_NUL_5") (pintype "passive"))
      (node (ref "U9") (pin "1") (pinfunction "+V_1") (pintype "passive"))
    )
    (net (code "52") (name "Net-(U10-ADJ)") (class "Default")
      (node (ref "R40") (pin "1") (pinfunction "1_1") (pintype "passive"))
      (node (ref "R42") (pin "2") (pinfunction "2_2") (pintype "passive"))
      (node (ref "U10") (pin "1") (pinfunction "ADJ_1") (pintype "input"))
    )
    (net (code "53") (name "Net-(U10-OUT)") (class "Default")
      (node (ref "C21") (pin "2") (pinfunction "2_2") (pintype "passive"))
      (node (ref "C23") (pin "1") (pinfunction "1_1") (pintype "passive"))
      (node (ref "F5") (pin "1") (pinfunction "1_1") (pintype "passive"))
      (node (ref "R40") (pin "2") (pinfunction "2_2") (pintype "passive"))
      (node (ref "U10") (pin "2") (pinfunction "OUT_2") (pintype "power_in"))
    )
    (net (code "54") (name "OP_OUT") (class "Default")
      (node (ref "C26") (pin "1") (pinfunction "1_1") (pintype "passive"))
      (node (ref "Q1") (pin "2") (pinfunction "E_2") (pintype "passive"))
      (node (ref "Q2") (pin "2") (pinfunction "E_2") (pintype "passive"))
      (node (ref "Q9") (pin "3") (pinfunction "E_3") (pintype "passive"))
      (node (ref "R1") (pin "2") (pinfunction "2_2") (pintype "passive"))
      (node (ref "R2") (pin "2") (pinfunction "2_2") (pintype "passive"))
      (node (ref "R20") (pin "2") (pinfunction "2_2") (pintype "passive"))
    )
    (net (code "55") (name "VCC_IN") (class "Default")
      (node (ref "C18") (pin "2") (pinfunction "2_2") (pintype "passive"))
      (node (ref "C24") (pin "2") (pinfunction "2_2") (pintype "passive"))
      (node (ref "C6") (pin "1") (pinfunction "1_1") (pintype "passive"))
      (node (ref "C7") (pin "2") (pinfunction "2_2") (pintype "passive"))
      (node (ref "P1") (pin "10") (pinfunction "10_10") (pintype "passive"))
      (node (ref "R35") (pin "2") (pinfunction "2_2") (pintype "passive"))
      (node (ref "U10") (pin "3") (pinfunction "IN_3") (pintype "power_in"))
      (node (ref "U4") (pin "2") (pinfunction "IN_2") (pintype "passive"))
      (node (ref "U7") (pin "3") (pinfunction "IN_3") (pintype "power_in"))
    )
    (net (code "56") (name "unconnected-(U1-NC-Pad1)") (class "Default")
      (node (ref "U1") (pin "1") (pinfunction "NC_1") (pintype "passive+no_connect"))
    )
    (net (code "57") (name "unconnected-(U1-NC-Pad8)") (class "Default")
      (node (ref "U1") (pin "8") (pinfunction "NC_8") (pintype "passive+no_connect"))
    )
    (net (code "58") (name "unconnected-(U3A-IN+-Pad3)") (class "Default")
      (node (ref "U3") (pin "3") (pinfunction "IN+_3") (pintype "input+no_connect"))
    )
    (net (code "59") (name "unconnected-(U3A-IN--Pad2)") (class "Default")
      (node (ref "U3") (pin "2") (pinfunction "IN-_2") (pintype "input+no_connect"))
    )
    (net (code "60") (name "unconnected-(U3A-OUT-Pad1)") (class "Default")
      (node (ref "U3") (pin "1") (pinfunction "OUT_1") (pintype "output+no_connect"))
    )
    (net (code "61") (name "unconnected-(U6-LV-Pad6)") (class "Default")
      (node (ref "U6") (pin "6") (pinfunction "LV_6") (pintype "input+no_connect"))
    )
    (net (code "62") (name "unconnected-(U6-NC-Pad1)") (class "Default")
      (node (ref "U6") (pin "1") (pinfunction "NC_1") (pintype "passive+no_connect"))
    )
    (net (code "63") (name "unconnected-(U6-OSC-Pad7)") (class "Default")
      (node (ref "U6") (pin "7") (pinfunction "OSC_7") (pintype "input+no_connect"))
    )
    (net (code "64") (name "unconnected-(U9-NC-Pad3)") (class "Default")
      (node (ref "U9") (pin "3") (pinfunction "NC_3") (pintype "passive+no_connect"))
    )
  )
)
